# IR_breakout.net
KiCad netlist of a schematic drawn in EAGLE
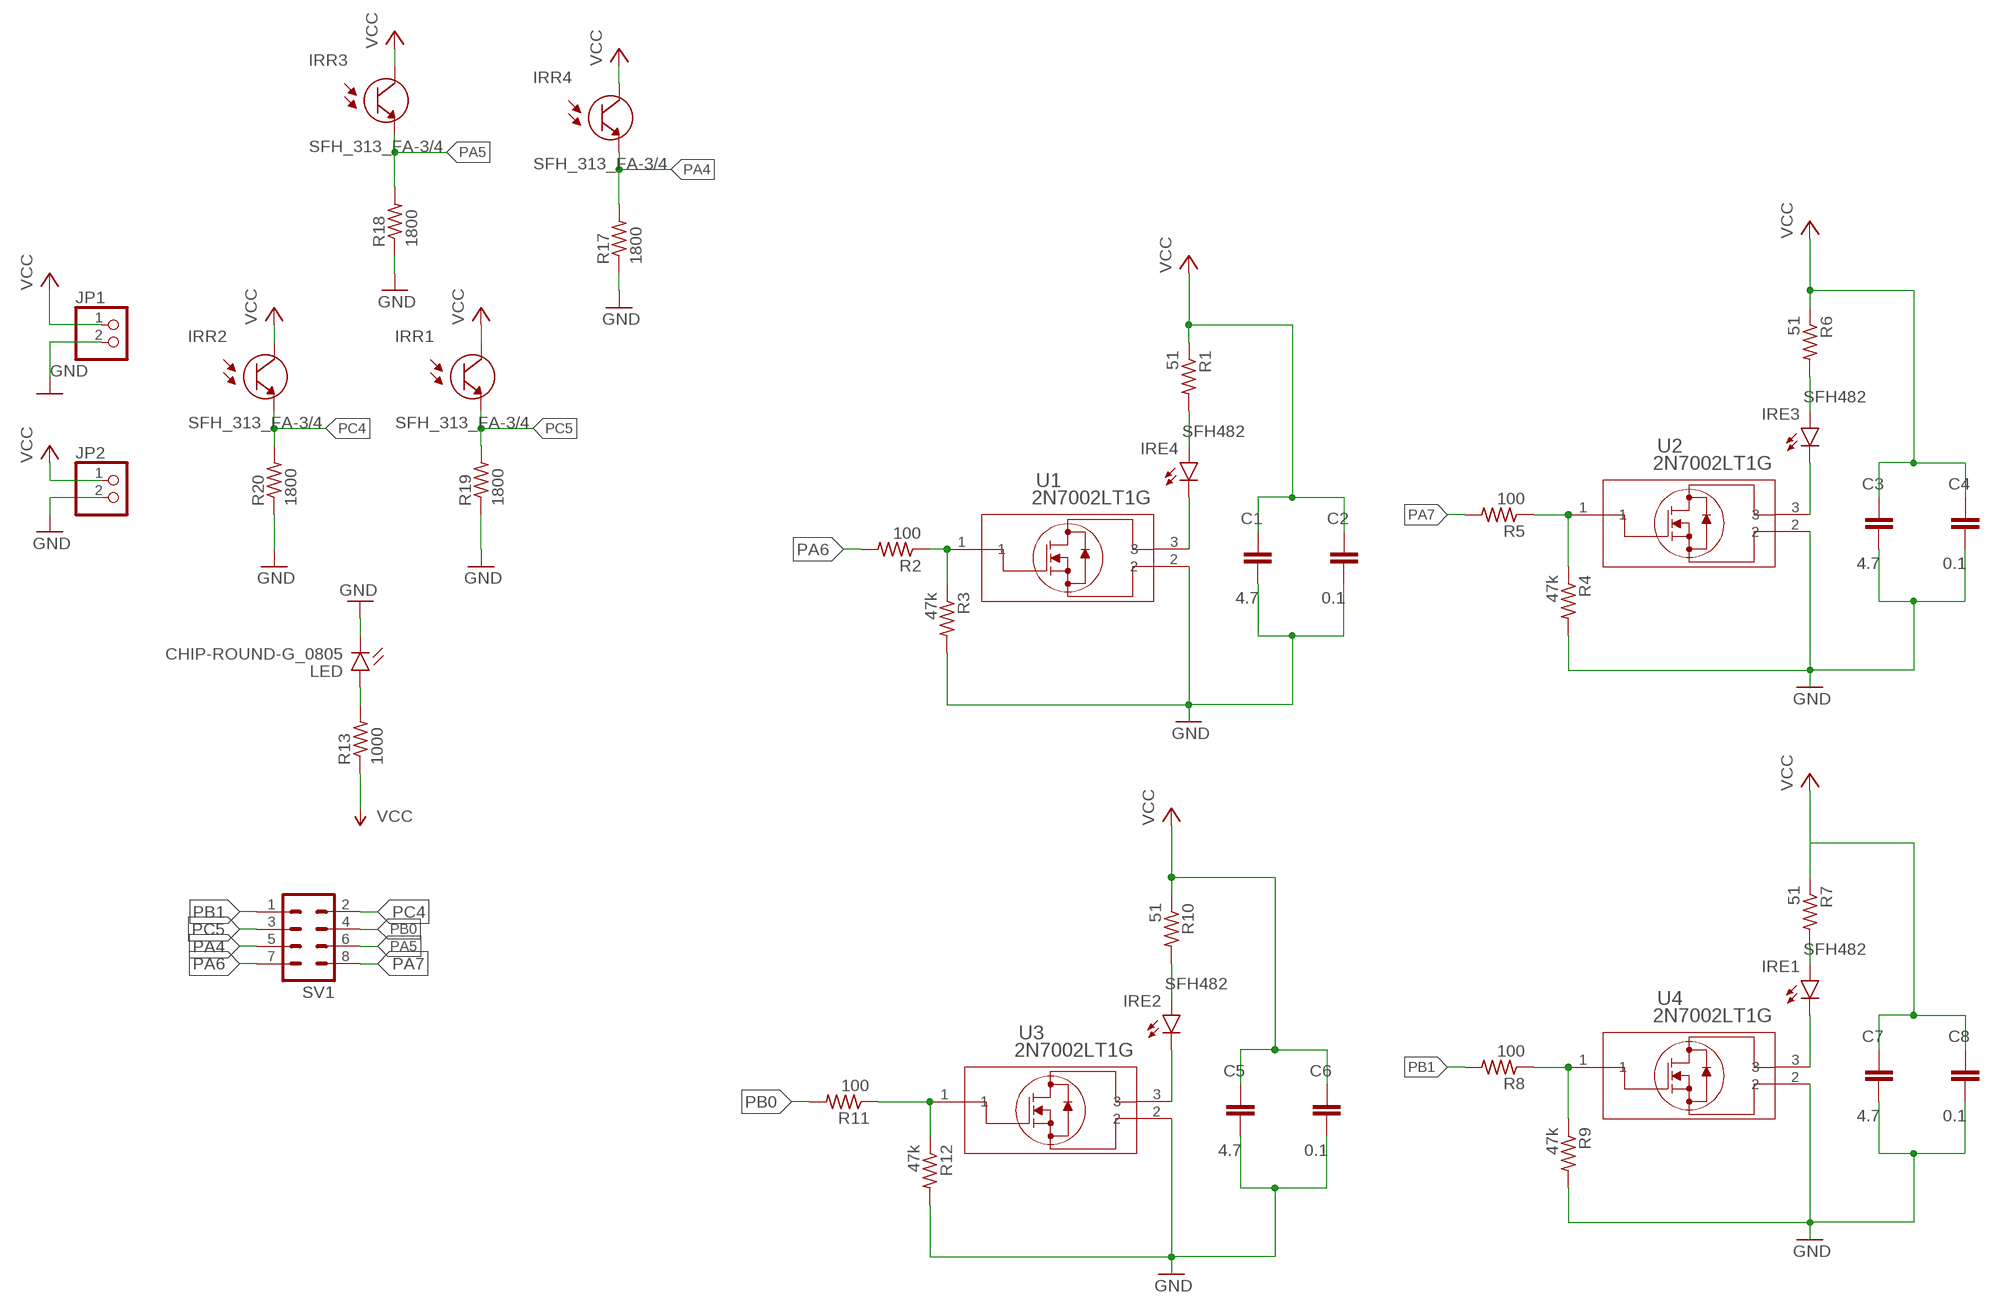
[diagram p0: schematic, sheet 1]

(export (version "E")
  (design (tool "Eeschema 10.0.6"))
  (components
    (comp (ref "C1")
      (value "4.7")
      (footprint "eagle-import:CAP_0805")
      (fields
        (field (name "DIGIKEY_PART_NUMBER") "311-1140-2-ND")
        (field (name "MANUFACTURER") "Yageo")
        (field (name "MPN") "CC0805KRX7R9BB104")
        (field (name "CREATED_BY") "PCBLayout.com")
      )
      (libsource (lib "eagle-import") (part "CC0805KRX7R9BB104"))
    )
    (comp (ref "C2")
      (value "0.1")
      (footprint "eagle-import:CAP_0805")
      (fields
        (field (name "DIGIKEY_PART_NUMBER") "311-1140-2-ND")
        (field (name "MANUFACTURER") "Yageo")
        (field (name "MPN") "CC0805KRX7R9BB104")
        (field (name "CREATED_BY") "PCBLayout.com")
      )
      (libsource (lib "eagle-import") (part "CC0805KRX7R9BB104"))
    )
    (comp (ref "C3")
      (value "4.7")
      (footprint "eagle-import:CAP_0805")
      (fields
        (field (name "DIGIKEY_PART_NUMBER") "311-1140-2-ND")
        (field (name "MANUFACTURER") "Yageo")
        (field (name "MPN") "CC0805KRX7R9BB104")
        (field (name "CREATED_BY") "PCBLayout.com")
      )
      (libsource (lib "eagle-import") (part "CC0805KRX7R9BB104"))
    )
    (comp (ref "C4")
      (value "0.1")
      (footprint "eagle-import:CAP_0805")
      (fields
        (field (name "DIGIKEY_PART_NUMBER") "311-1140-2-ND")
        (field (name "MANUFACTURER") "Yageo")
        (field (name "MPN") "CC0805KRX7R9BB104")
        (field (name "CREATED_BY") "PCBLayout.com")
      )
      (libsource (lib "eagle-import") (part "CC0805KRX7R9BB104"))
    )
    (comp (ref "C5")
      (value "4.7")
      (footprint "eagle-import:CAP_0805")
      (fields
        (field (name "DIGIKEY_PART_NUMBER") "311-1140-2-ND")
        (field (name "MANUFACTURER") "Yageo")
        (field (name "MPN") "CC0805KRX7R9BB104")
        (field (name "CREATED_BY") "PCBLayout.com")
      )
      (libsource (lib "eagle-import") (part "CC0805KRX7R9BB104"))
    )
    (comp (ref "C6")
      (value "0.1")
      (footprint "eagle-import:CAP_0805")
      (fields
        (field (name "DIGIKEY_PART_NUMBER") "311-1140-2-ND")
        (field (name "MANUFACTURER") "Yageo")
        (field (name "MPN") "CC0805KRX7R9BB104")
        (field (name "CREATED_BY") "PCBLayout.com")
      )
      (libsource (lib "eagle-import") (part "CC0805KRX7R9BB104"))
    )
    (comp (ref "C7")
      (value "4.7")
      (footprint "eagle-import:CAP_0805")
      (fields
        (field (name "DIGIKEY_PART_NUMBER") "311-1140-2-ND")
        (field (name "MANUFACTURER") "Yageo")
        (field (name "MPN") "CC0805KRX7R9BB104")
        (field (name "CREATED_BY") "PCBLayout.com")
      )
      (libsource (lib "eagle-import") (part "CC0805KRX7R9BB104"))
    )
    (comp (ref "C8")
      (value "0.1")
      (footprint "eagle-import:CAP_0805")
      (fields
        (field (name "DIGIKEY_PART_NUMBER") "311-1140-2-ND")
        (field (name "MANUFACTURER") "Yageo")
        (field (name "MPN") "CC0805KRX7R9BB104")
        (field (name "CREATED_BY") "PCBLayout.com")
      )
      (libsource (lib "eagle-import") (part "CC0805KRX7R9BB104"))
    )
    (comp (ref "IRE1")
      (value "SFH482")
      (footprint "eagle-import:SFH482")
      (libsource (lib "eagle-import") (part "SFH482"))
    )
    (comp (ref "IRE2")
      (value "SFH482")
      (footprint "eagle-import:SFH482")
      (libsource (lib "eagle-import") (part "SFH482"))
    )
    (comp (ref "IRE3")
      (value "SFH482")
      (footprint "eagle-import:SFH482")
      (libsource (lib "eagle-import") (part "SFH482"))
    )
    (comp (ref "IRE4")
      (value "SFH482")
      (footprint "eagle-import:SFH482")
      (libsource (lib "eagle-import") (part "SFH482"))
    )
    (comp (ref "IRR1")
      (value "SFH_313_FA-3/4")
      (footprint "eagle-import:XDCR_SFH_313_FA-3_4")
      (fields (field (name "MF") "OSRAM Opto") (field (name "MP") "SFH 313 FA-3/4"))
      (libsource (lib "eagle-import") (part "SFH_313_FA-3/4"))
    )
    (comp (ref "IRR2")
      (value "SFH_313_FA-3/4")
      (footprint "eagle-import:XDCR_SFH_313_FA-3_4")
      (fields (field (name "MF") "OSRAM Opto") (field (name "MP") "SFH 313 FA-3/4"))
      (libsource (lib "eagle-import") (part "SFH_313_FA-3/4"))
    )
    (comp (ref "IRR3")
      (value "SFH_313_FA-3/4")
      (footprint "eagle-import:XDCR_SFH_313_FA-3_4")
      (fields (field (name "MF") "OSRAM Opto") (field (name "MP") "SFH 313 FA-3/4"))
      (libsource (lib "eagle-import") (part "SFH_313_FA-3/4"))
    )
    (comp (ref "IRR4")
      (value "SFH_313_FA-3/4")
      (footprint "eagle-import:XDCR_SFH_313_FA-3_4")
      (fields (field (name "MF") "OSRAM Opto") (field (name "MP") "SFH 313 FA-3/4"))
      (libsource (lib "eagle-import") (part "SFH_313_FA-3/4"))
    )
    (comp (ref "JP1")
      (value "PINHD-1X2")
      (footprint "eagle-import:1X02")
      (libsource (lib "eagle-import") (part "PINHD-1X2"))
    )
    (comp (ref "JP2")
      (value "PINHD-1X2")
      (footprint "eagle-import:1X02")
      (libsource (lib "eagle-import") (part "PINHD-1X2"))
    )
    (comp (ref "LED")
      (value "CHIP-ROUND-G_0805")
      (footprint "eagle-import:LEDC2012X105N_RND-G")
      (libsource (lib "eagle-import") (part "CHIP-ROUND-G_0805"))
    )
    (comp (ref "R1")
      (value "51")
      (footprint "eagle-import:RES_0805")
      (fields
        (field (name "DIGIKEY_PART_NUMBER") "541-0.0ATR-ND")
        (field (name "MANUFACTURER") "Vishay Dale")
        (field (name "MPN") "CRCW08050000Z0EA")
        (field (name "CREATED_BY") "PCBLayout.com")
      )
      (libsource (lib "eagle-import") (part "CRCW08050000Z0EA"))
    )
    (comp (ref "R2")
      (value "100")
      (footprint "eagle-import:RES_0805")
      (fields
        (field (name "DIGIKEY_PART_NUMBER") "541-0.0ATR-ND")
        (field (name "MANUFACTURER") "Vishay Dale")
        (field (name "MPN") "CRCW08050000Z0EA")
        (field (name "CREATED_BY") "PCBLayout.com")
      )
      (libsource (lib "eagle-import") (part "CRCW08050000Z0EA"))
    )
    (comp (ref "R3")
      (value "47k")
      (footprint "eagle-import:RES_0805")
      (fields
        (field (name "DIGIKEY_PART_NUMBER") "541-0.0ATR-ND")
        (field (name "MANUFACTURER") "Vishay Dale")
        (field (name "MPN") "CRCW08050000Z0EA")
        (field (name "CREATED_BY") "PCBLayout.com")
      )
      (libsource (lib "eagle-import") (part "CRCW08050000Z0EA"))
    )
    (comp (ref "R4")
      (value "47k")
      (footprint "eagle-import:RES_0805")
      (fields
        (field (name "DIGIKEY_PART_NUMBER") "541-0.0ATR-ND")
        (field (name "MANUFACTURER") "Vishay Dale")
        (field (name "MPN") "CRCW08050000Z0EA")
        (field (name "CREATED_BY") "PCBLayout.com")
      )
      (libsource (lib "eagle-import") (part "CRCW08050000Z0EA"))
    )
    (comp (ref "R5")
      (value "100")
      (footprint "eagle-import:RES_0805")
      (fields
        (field (name "DIGIKEY_PART_NUMBER") "541-0.0ATR-ND")
        (field (name "MANUFACTURER") "Vishay Dale")
        (field (name "MPN") "CRCW08050000Z0EA")
        (field (name "CREATED_BY") "PCBLayout.com")
      )
      (libsource (lib "eagle-import") (part "CRCW08050000Z0EA"))
    )
    (comp (ref "R6")
      (value "51")
      (footprint "eagle-import:RES_0805")
      (fields
        (field (name "DIGIKEY_PART_NUMBER") "541-0.0ATR-ND")
        (field (name "MANUFACTURER") "Vishay Dale")
        (field (name "MPN") "CRCW08050000Z0EA")
        (field (name "CREATED_BY") "PCBLayout.com")
      )
      (libsource (lib "eagle-import") (part "CRCW08050000Z0EA"))
    )
    (comp (ref "R7")
      (value "51")
      (footprint "eagle-import:RES_0805")
      (fields
        (field (name "DIGIKEY_PART_NUMBER") "541-0.0ATR-ND")
        (field (name "MANUFACTURER") "Vishay Dale")
        (field (name "MPN") "CRCW08050000Z0EA")
        (field (name "CREATED_BY") "PCBLayout.com")
      )
      (libsource (lib "eagle-import") (part "CRCW08050000Z0EA"))
    )
    (comp (ref "R8")
      (value "100")
      (footprint "eagle-import:RES_0805")
      (fields
        (field (name "DIGIKEY_PART_NUMBER") "541-0.0ATR-ND")
        (field (name "MANUFACTURER") "Vishay Dale")
        (field (name "MPN") "CRCW08050000Z0EA")
        (field (name "CREATED_BY") "PCBLayout.com")
      )
      (libsource (lib "eagle-import") (part "CRCW08050000Z0EA"))
    )
    (comp (ref "R9")
      (value "47k")
      (footprint "eagle-import:RES_0805")
      (fields
        (field (name "DIGIKEY_PART_NUMBER") "541-0.0ATR-ND")
        (field (name "MANUFACTURER") "Vishay Dale")
        (field (name "MPN") "CRCW08050000Z0EA")
        (field (name "CREATED_BY") "PCBLayout.com")
      )
      (libsource (lib "eagle-import") (part "CRCW08050000Z0EA"))
    )
    (comp (ref "R10")
      (value "51")
      (footprint "eagle-import:RES_0805")
      (fields
        (field (name "DIGIKEY_PART_NUMBER") "541-0.0ATR-ND")
        (field (name "MANUFACTURER") "Vishay Dale")
        (field (name "MPN") "CRCW08050000Z0EA")
        (field (name "CREATED_BY") "PCBLayout.com")
      )
      (libsource (lib "eagle-import") (part "CRCW08050000Z0EA"))
    )
    (comp (ref "R11")
      (value "100")
      (footprint "eagle-import:RES_0805")
      (fields
        (field (name "DIGIKEY_PART_NUMBER") "541-0.0ATR-ND")
        (field (name "MANUFACTURER") "Vishay Dale")
        (field (name "MPN") "CRCW08050000Z0EA")
        (field (name "CREATED_BY") "PCBLayout.com")
      )
      (libsource (lib "eagle-import") (part "CRCW08050000Z0EA"))
    )
    (comp (ref "R12")
      (value "47k")
      (footprint "eagle-import:RES_0805")
      (fields
        (field (name "DIGIKEY_PART_NUMBER") "541-0.0ATR-ND")
        (field (name "MANUFACTURER") "Vishay Dale")
        (field (name "MPN") "CRCW08050000Z0EA")
        (field (name "CREATED_BY") "PCBLayout.com")
      )
      (libsource (lib "eagle-import") (part "CRCW08050000Z0EA"))
    )
    (comp (ref "R13")
      (value "1000")
      (footprint "eagle-import:RES_0805")
      (fields
        (field (name "DIGIKEY_PART_NUMBER") "541-0.0ATR-ND")
        (field (name "MANUFACTURER") "Vishay Dale")
        (field (name "MPN") "CRCW08050000Z0EA")
        (field (name "CREATED_BY") "PCBLayout.com")
      )
      (libsource (lib "eagle-import") (part "CRCW08050000Z0EA"))
    )
    (comp (ref "R17")
      (value "1800")
      (footprint "eagle-import:RES_0805")
      (fields
        (field (name "DIGIKEY_PART_NUMBER") "541-0.0ATR-ND")
        (field (name "MANUFACTURER") "Vishay Dale")
        (field (name "MPN") "CRCW08050000Z0EA")
        (field (name "CREATED_BY") "PCBLayout.com")
      )
      (libsource (lib "eagle-import") (part "CRCW08050000Z0EA"))
    )
    (comp (ref "R18")
      (value "1800")
      (footprint "eagle-import:RES_0805")
      (fields
        (field (name "DIGIKEY_PART_NUMBER") "541-0.0ATR-ND")
        (field (name "MANUFACTURER") "Vishay Dale")
        (field (name "MPN") "CRCW08050000Z0EA")
        (field (name "CREATED_BY") "PCBLayout.com")
      )
      (libsource (lib "eagle-import") (part "CRCW08050000Z0EA"))
    )
    (comp (ref "R19")
      (value "1800")
      (footprint "eagle-import:RES_0805")
      (fields
        (field (name "DIGIKEY_PART_NUMBER") "541-0.0ATR-ND")
        (field (name "MANUFACTURER") "Vishay Dale")
        (field (name "MPN") "CRCW08050000Z0EA")
        (field (name "CREATED_BY") "PCBLayout.com")
      )
      (libsource (lib "eagle-import") (part "CRCW08050000Z0EA"))
    )
    (comp (ref "R20")
      (value "1800")
      (footprint "eagle-import:RES_0805")
      (fields
        (field (name "DIGIKEY_PART_NUMBER") "541-0.0ATR-ND")
        (field (name "MANUFACTURER") "Vishay Dale")
        (field (name "MPN") "CRCW08050000Z0EA")
        (field (name "CREATED_BY") "PCBLayout.com")
      )
      (libsource (lib "eagle-import") (part "CRCW08050000Z0EA"))
    )
    (comp (ref "SV1")
      (value "MA04-2")
      (footprint "eagle-import:MA04-2")
      (libsource (lib "eagle-import") (part "MA04-2"))
    )
    (comp (ref "U1")
      (value "2N7002LT1G")
      (footprint "eagle-import:SOT-23_3L_ONS")
      (fields (field (name "COPYRIGHT") "Copyright (C) 2018 Accelerated Designs. All rights reserved"))
      (libsource (lib "eagle-import") (part "2N7002LT1G"))
    )
    (comp (ref "U2")
      (value "2N7002LT1G")
      (footprint "eagle-import:SOT-23_3L_ONS")
      (fields (field (name "COPYRIGHT") "Copyright (C) 2018 Accelerated Designs. All rights reserved"))
      (libsource (lib "eagle-import") (part "2N7002LT1G"))
    )
    (comp (ref "U3")
      (value "2N7002LT1G")
      (footprint "eagle-import:SOT-23_3L_ONS")
      (fields (field (name "COPYRIGHT") "Copyright (C) 2018 Accelerated Designs. All rights reserved"))
      (libsource (lib "eagle-import") (part "2N7002LT1G"))
    )
    (comp (ref "U4")
      (value "2N7002LT1G")
      (footprint "eagle-import:SOT-23_3L_ONS")
      (fields (field (name "COPYRIGHT") "Copyright (C) 2018 Accelerated Designs. All rights reserved"))
      (libsource (lib "eagle-import") (part "2N7002LT1G"))
    )
  )
  (nets
    (net (code "1") (name "GND") (class "Default")
      (node (ref "C1") (pin "2") (pinfunction "2_2") (pintype "passive"))
      (node (ref "C2") (pin "2") (pinfunction "2_2") (pintype "passive"))
      (node (ref "C3") (pin "2") (pinfunction "2_2") (pintype "passive"))
      (node (ref "C4") (pin "2") (pinfunction "2_2") (pintype "passive"))
      (node (ref "C5") (pin "2") (pinfunction "2_2") (pintype "passive"))
      (node (ref "C6") (pin "2") (pinfunction "2_2") (pintype "passive"))
      (node (ref "C7") (pin "2") (pinfunction "2_2") (pintype "passive"))
      (node (ref "C8") (pin "2") (pinfunction "2_2") (pintype "passive"))
      (node (ref "JP1") (pin "2") (pinfunction "2_2") (pintype "passive"))
      (node (ref "JP2") (pin "2") (pinfunction "2_2") (pintype "passive"))
      (node (ref "LED") (pin "C") (pinfunction "C_C") (pintype "passive"))
      (node (ref "R12") (pin "2") (pinfunction "2_2") (pintype "passive"))
      (node (ref "R17") (pin "1") (pinfunction "1_1") (pintype "passive"))
      (node (ref "R18") (pin "1") (pinfunction "1_1") (pintype "passive"))
      (node (ref "R19") (pin "1") (pinfunction "1_1") (pintype "passive"))
      (node (ref "R20") (pin "1") (pinfunction "1_1") (pintype "passive"))
      (node (ref "R3") (pin "2") (pinfunction "2_2") (pintype "passive"))
      (node (ref "R4") (pin "2") (pinfunction "2_2") (pintype "passive"))
      (node (ref "R9") (pin "2") (pinfunction "2_2") (pintype "passive"))
      (node (ref "U1") (pin "2") (pinfunction "2_2") (pintype "passive"))
      (node (ref "U2") (pin "2") (pinfunction "2_2") (pintype "passive"))
      (node (ref "U3") (pin "2") (pinfunction "2_2") (pintype "passive"))
      (node (ref "U4") (pin "2") (pinfunction "2_2") (pintype "passive"))
    )
    (net (code "2") (name "Net-(IRE1-C)") (class "Default")
      (node (ref "IRE1") (pin "K") (pinfunction "C_K") (pintype "passive"))
      (node (ref "U4") (pin "3") (pinfunction "3_3") (pintype "passive"))
    )
    (net (code "3") (name "Net-(IRE1-PadA)") (class "Default")
      (node (ref "IRE1") (pin "A") (pinfunction "A_A") (pintype "passive"))
      (node (ref "R7") (pin "2") (pinfunction "2_2") (pintype "passive"))
    )
    (net (code "4") (name "Net-(IRE2-C)") (class "Default")
      (node (ref "IRE2") (pin "K") (pinfunction "C_K") (pintype "passive"))
      (node (ref "U3") (pin "3") (pinfunction "3_3") (pintype "passive"))
    )
    (net (code "5") (name "Net-(IRE2-PadA)") (class "Default")
      (node (ref "IRE2") (pin "A") (pinfunction "A_A") (pintype "passive"))
      (node (ref "R10") (pin "2") (pinfunction "2_2") (pintype "passive"))
    )
    (net (code "6") (name "Net-(IRE3-C)") (class "Default")
      (node (ref "IRE3") (pin "K") (pinfunction "C_K") (pintype "passive"))
      (node (ref "U2") (pin "3") (pinfunction "3_3") (pintype "passive"))
    )
    (net (code "7") (name "Net-(IRE3-PadA)") (class "Default")
      (node (ref "IRE3") (pin "A") (pinfunction "A_A") (pintype "passive"))
      (node (ref "R6") (pin "2") (pinfunction "2_2") (pintype "passive"))
    )
    (net (code "8") (name "Net-(IRE4-C)") (class "Default")
      (node (ref "IRE4") (pin "K") (pinfunction "C_K") (pintype "passive"))
      (node (ref "U1") (pin "3") (pinfunction "3_3") (pintype "passive"))
    )
    (net (code "9") (name "Net-(IRE4-PadA)") (class "Default")
      (node (ref "IRE4") (pin "A") (pinfunction "A_A") (pintype "passive"))
      (node (ref "R1") (pin "2") (pinfunction "2_2") (pintype "passive"))
    )
    (net (code "10") (name "Net-(LED-PadA)") (class "Default")
      (node (ref "LED") (pin "A") (pinfunction "A_A") (pintype "passive"))
      (node (ref "R13") (pin "2") (pinfunction "2_2") (pintype "passive"))
    )
    (net (code "11") (name "Net-(R2-Pad1)") (class "Default")
      (node (ref "R2") (pin "1") (pinfunction "1_1") (pintype "passive"))
      (node (ref "R3") (pin "1") (pinfunction "1_1") (pintype "passive"))
      (node (ref "U1") (pin "1") (pinfunction "1_1") (pintype "passive"))
    )
    (net (code "12") (name "Net-(R4-Pad1)") (class "Default")
      (node (ref "R4") (pin "1") (pinfunction "1_1") (pintype "passive"))
      (node (ref "R5") (pin "1") (pinfunction "1_1") (pintype "passive"))
      (node (ref "U2") (pin "1") (pinfunction "1_1") (pintype "passive"))
    )
    (net (code "13") (name "Net-(R8-Pad1)") (class "Default")
      (node (ref "R8") (pin "1") (pinfunction "1_1") (pintype "passive"))
      (node (ref "R9") (pin "1") (pinfunction "1_1") (pintype "passive"))
      (node (ref "U4") (pin "1") (pinfunction "1_1") (pintype "passive"))
    )
    (net (code "14") (name "Net-(R11-Pad1)") (class "Default")
      (node (ref "R11") (pin "1") (pinfunction "1_1") (pintype "passive"))
      (node (ref "R12") (pin "1") (pinfunction "1_1") (pintype "passive"))
      (node (ref "U3") (pin "1") (pinfunction "1_1") (pintype "passive"))
    )
    (net (code "15") (name "PA4") (class "Default")
      (node (ref "IRR4") (pin "1") (pinfunction "E_1") (pintype "passive"))
      (node (ref "R17") (pin "2") (pinfunction "2_2") (pintype "passive"))
      (node (ref "SV1") (pin "5") (pinfunction "5_5") (pintype "passive"))
    )
    (net (code "16") (name "PA5") (class "Default")
      (node (ref "IRR3") (pin "1") (pinfunction "E_1") (pintype "passive"))
      (node (ref "R18") (pin "2") (pinfunction "2_2") (pintype "passive"))
      (node (ref "SV1") (pin "6") (pinfunction "6_6") (pintype "passive"))
    )
    (net (code "17") (name "PA6") (class "Default")
      (node (ref "R2") (pin "2") (pinfunction "2_2") (pintype "passive"))
      (node (ref "SV1") (pin "7") (pinfunction "7_7") (pintype "passive"))
    )
    (net (code "18") (name "PA7") (class "Default")
      (node (ref "R5") (pin "2") (pinfunction "2_2") (pintype "passive"))
      (node (ref "SV1") (pin "8") (pinfunction "8_8") (pintype "passive"))
    )
    (net (code "19") (name "PB0") (class "Default")
      (node (ref "R11") (pin "2") (pinfunction "2_2") (pintype "passive"))
      (node (ref "SV1") (pin "4") (pinfunction "4_4") (pintype "passive"))
    )
    (net (code "20") (name "PB1") (class "Default")
      (node (ref "R8") (pin "2") (pinfunction "2_2") (pintype "passive"))
      (node (ref "SV1") (pin "1") (pinfunction "1_1") (pintype "passive"))
    )
    (net (code "21") (name "PC4") (class "Default")
      (node (ref "IRR2") (pin "1") (pinfunction "E_1") (pintype "passive"))
      (node (ref "R20") (pin "2") (pinfunction "2_2") (pintype "passive"))
      (node (ref "SV1") (pin "2") (pinfunction "2_2") (pintype "passive"))
    )
    (net (code "22") (name "PC5") (class "Default")
      (node (ref "IRR1") (pin "1") (pinfunction "E_1") (pintype "passive"))
      (node (ref "R19") (pin "2") (pinfunction "2_2") (pintype "passive"))
      (node (ref "SV1") (pin "3") (pinfunction "3_3") (pintype "passive"))
    )
    (net (code "23") (name "VCC") (class "Default")
      (node (ref "C1") (pin "1") (pinfunction "1_1") (pintype "passive"))
      (node (ref "C2") (pin "1") (pinfunction "1_1") (pintype "passive"))
      (node (ref "C3") (pin "1") (pinfunction "1_1") (pintype "passive"))
      (node (ref "C4") (pin "1") (pinfunction "1_1") (pintype "passive"))
      (node (ref "C5") (pin "1") (pinfunction "1_1") (pintype "passive"))
      (node (ref "C6") (pin "1") (pinfunction "1_1") (pintype "passive"))
      (node (ref "C7") (pin "1") (pinfunction "1_1") (pintype "passive"))
      (node (ref "C8") (pin "1") (pinfunction "1_1") (pintype "passive"))
      (node (ref "IRR1") (pin "2") (pinfunction "C_2") (pintype "passive"))
      (node (ref "IRR2") (pin "2") (pinfunction "C_2") (pintype "passive"))
      (node (ref "IRR3") (pin "2") (pinfunction "C_2") (pintype "passive"))
      (node (ref "IRR4") (pin "2") (pinfunction "C_2") (pintype "passive"))
      (node (ref "JP1") (pin "1") (pinfunction "1_1") (pintype "passive"))
      (node (ref "JP2") (pin "1") (pinfunction "1_1") (pintype "passive"))
      (node (ref "R1") (pin "1") (pinfunction "1_1") (pintype "passive"))
      (node (ref "R10") (pin "1") (pinfunction "1_1") (pintype "passive"))
      (node (ref "R13") (pin "1") (pinfunction "1_1") (pintype "passive"))
      (node (ref "R6") (pin "1") (pinfunction "1_1") (pintype "passive"))
      (node (ref "R7") (pin "1") (pinfunction "1_1") (pintype "passive"))
    )
  )
)
